# Task.net
KiCad netlist of a schematic drawn in EAGLE
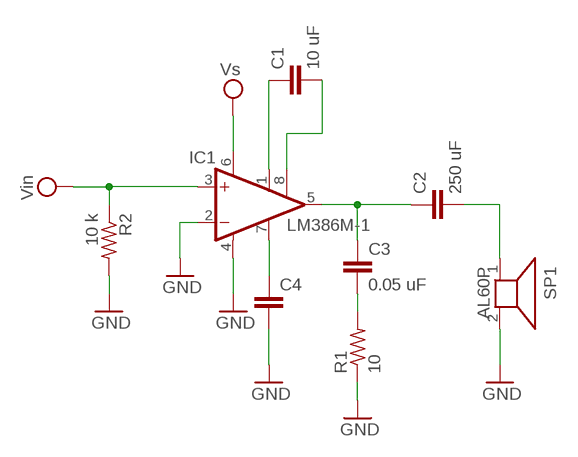
[diagram p0: schematic, sheet 1]

(export (version "E")
  (design (tool "Eeschema 10.0.6"))
  (components
    (comp (ref "C1")
      (value "10 uF")
      (footprint "eagle-import:C5B3")
      (libsource (lib "eagle-import") (part "C5/3"))
    )
    (comp (ref "C2")
      (value "250 uF")
      (footprint "eagle-import:C5B3")
      (libsource (lib "eagle-import") (part "C5/3"))
    )
    (comp (ref "C3")
      (value "0.05 uF")
      (footprint "eagle-import:C5B3")
      (libsource (lib "eagle-import") (part "C5/3"))
    )
    (comp (ref "C4")
      (value "C5/3")
      (footprint "eagle-import:C5B3")
      (libsource (lib "eagle-import") (part "C5/3"))
    )
    (comp (ref "IC1")
      (value "LM386M-1")
      (footprint "eagle-import:SO08")
      (libsource (lib "eagle-import") (part "LM386?-M1"))
    )
    (comp (ref "R1")
      (value "10")
      (footprint "eagle-import:M0805")
      (libsource (lib "eagle-import") (part "R-US_M0805"))
    )
    (comp (ref "R2")
      (value "10 k")
      (footprint "eagle-import:M0805")
      (libsource (lib "eagle-import") (part "R-US_M0805"))
    )
    (comp (ref "SP1")
      (value "AL60P")
      (footprint "eagle-import:AL60P")
      (libsource (lib "eagle-import") (part "AL60P"))
    )
  )
  (nets
    (net (code "1") (name "GND") (class "Default")
      (node (ref "C4") (pin "2") (pinfunction "2_2") (pintype "passive"))
      (node (ref "IC1") (pin "2") (pinfunction "-IN_2") (pintype "input"))
      (node (ref "IC1") (pin "4") (pinfunction "GND_4") (pintype "power_in"))
      (node (ref "R1") (pin "1") (pinfunction "1_1") (pintype "passive"))
      (node (ref "R2") (pin "2") (pinfunction "2_2") (pintype "passive"))
      (node (ref "SP1") (pin "2") (pinfunction "2_2") (pintype "passive"))
    )
    (net (code "2") (name "Net-(C1-Pad1)") (class "Default")
      (node (ref "C1") (pin "1") (pinfunction "1_1") (pintype "passive"))
      (node (ref "IC1") (pin "1") (pinfunction "GAIN_1") (pintype "passive"))
    )
    (net (code "3") (name "Net-(C1-Pad2)") (class "Default")
      (node (ref "C1") (pin "2") (pinfunction "2_2") (pintype "passive"))
      (node (ref "IC1") (pin "8") (pinfunction "GAIN_8") (pintype "passive"))
    )
    (net (code "4") (name "Net-(C2-Pad2)") (class "Default")
      (node (ref "C2") (pin "2") (pinfunction "2_2") (pintype "passive"))
      (node (ref "SP1") (pin "1") (pinfunction "1_1") (pintype "passive"))
    )
    (net (code "5") (name "Net-(C3-Pad2)") (class "Default")
      (node (ref "C3") (pin "2") (pinfunction "2_2") (pintype "passive"))
      (node (ref "R1") (pin "2") (pinfunction "2_2") (pintype "passive"))
    )
    (net (code "6") (name "Net-(IC1-BYPASS)") (class "Default")
      (node (ref "C4") (pin "1") (pinfunction "1_1") (pintype "passive"))
      (node (ref "IC1") (pin "7") (pinfunction "BYPASS_7") (pintype "passive"))
    )
    (net (code "7") (name "Net-(IC1-OUT)") (class "Default")
      (node (ref "C2") (pin "1") (pinfunction "1_1") (pintype "passive"))
      (node (ref "C3") (pin "1") (pinfunction "1_1") (pintype "passive"))
      (node (ref "IC1") (pin "5") (pinfunction "OUT_5") (pintype "output"))
    )
    (net (code "8") (name "Vin") (class "Default")
      (node (ref "IC1") (pin "3") (pinfunction "+IN_3") (pintype "input"))
      (node (ref "IC1") (pin "6") (pinfunction "VS_6") (pintype "power_in"))
      (node (ref "R2") (pin "1") (pinfunction "1_1") (pintype "passive"))
    )
  )
)
